# HomeAutomationModuleV2.net
KiCad netlist of a schematic drawn in EAGLE
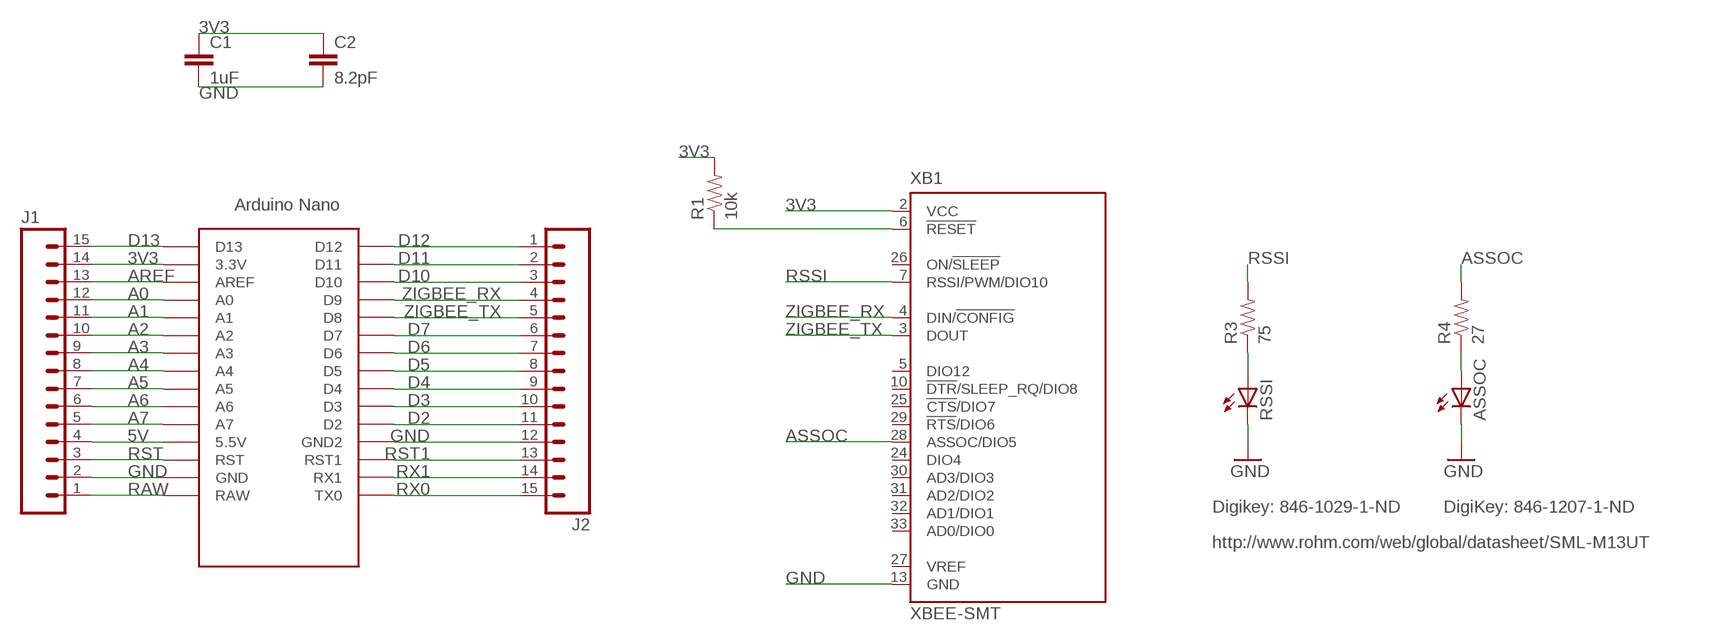
[diagram p0: schematic, sheet 1]

(export (version "E")
  (design (tool "Eeschema 10.0.6"))
  (components
    (comp (ref "ASSOC")
      (value "LEDCHIP-LED0805")
      (footprint "eagle-import:CHIP-LED0805")
      (libsource (lib "eagle-import") (part "LEDCHIP-LED0805"))
    )
    (comp (ref "C1")
      (value "1uF")
      (footprint "eagle-import:0805-CAP")
      (libsource (lib "eagle-import") (part "0.33UF-50V-10%(0805)"))
    )
    (comp (ref "C2")
      (value "8.2pF")
      (footprint "eagle-import:0805-CAP")
      (libsource (lib "eagle-import") (part "0.33UF-50V-10%(0805)"))
    )
    (comp (ref "J1")
      (value "M15")
      (footprint "eagle-import:1X15")
      (libsource (lib "eagle-import") (part "M15"))
    )
    (comp (ref "J2")
      (value "M15")
      (footprint "eagle-import:1X15")
      (libsource (lib "eagle-import") (part "M15"))
    )
    (comp (ref "R1")
      (value "10k")
      (footprint "eagle-import:0805")
      (libsource (lib "eagle-import") (part "0.3OHM-1/8W-1%(0805)"))
    )
    (comp (ref "R3")
      (value "75")
      (footprint "eagle-import:0805")
      (libsource (lib "eagle-import") (part "RESISTOR0805-RES"))
    )
    (comp (ref "R4")
      (value "27")
      (footprint "eagle-import:0805")
      (libsource (lib "eagle-import") (part "RESISTOR0805-RES"))
    )
    (comp (ref "RSSI")
      (value "LEDCHIP-LED0805")
      (footprint "eagle-import:CHIP-LED0805")
      (libsource (lib "eagle-import") (part "LEDCHIP-LED0805"))
    )
    (comp (ref "U$1")
      (value "NANO")
      (footprint "eagle-import:NANO")
      (libsource (lib "eagle-import") (part "NANO"))
    )
    (comp (ref "XB1")
      (value "XBEE-SMT")
      (footprint "eagle-import:XBEE-SMT")
      (libsource (lib "eagle-import") (part "XBEE-SMT"))
    )
  )
  (nets
    (net (code "1") (name "/3V3") (class "Default")
      (node (ref "C1") (pin "1") (pinfunction "1_1") (pintype "passive"))
      (node (ref "C2") (pin "1") (pinfunction "1_1") (pintype "passive"))
      (node (ref "J1") (pin "14") (pinfunction "14_14") (pintype "passive"))
      (node (ref "R1") (pin "2") (pinfunction "2_2") (pintype "passive"))
      (node (ref "U$1") (pin "3.3V") (pinfunction "3.3V_3.3V") (pintype "bidirectional"))
      (node (ref "XB1") (pin "2") (pinfunction "VCC_2") (pintype "power_in"))
    )
    (net (code "2") (name "/5V") (class "Default")
      (node (ref "J1") (pin "4") (pinfunction "4_4") (pintype "passive"))
      (node (ref "U$1") (pin "5V") (pinfunction "5.5V_5V") (pintype "bidirectional"))
    )
    (net (code "3") (name "/A0") (class "Default")
      (node (ref "J1") (pin "12") (pinfunction "12_12") (pintype "passive"))
      (node (ref "U$1") (pin "A0") (pinfunction "A0_A0") (pintype "bidirectional"))
    )
    (net (code "4") (name "/A1") (class "Default")
      (node (ref "J1") (pin "11") (pinfunction "11_11") (pintype "passive"))
      (node (ref "U$1") (pin "A1") (pinfunction "A1_A1") (pintype "bidirectional"))
    )
    (net (code "5") (name "/A2") (class "Default")
      (node (ref "J1") (pin "10") (pinfunction "10_10") (pintype "passive"))
      (node (ref "U$1") (pin "A2") (pinfunction "A2_A2") (pintype "bidirectional"))
    )
    (net (code "6") (name "/A3") (class "Default")
      (node (ref "J1") (pin "9") (pinfunction "9_9") (pintype "passive"))
      (node (ref "U$1") (pin "A3") (pinfunction "A3_A3") (pintype "bidirectional"))
    )
    (net (code "7") (name "/A4") (class "Default")
      (node (ref "J1") (pin "8") (pinfunction "8_8") (pintype "passive"))
      (node (ref "U$1") (pin "A4") (pinfunction "A4_A4") (pintype "bidirectional"))
    )
    (net (code "8") (name "/A5") (class "Default")
      (node (ref "J1") (pin "7") (pinfunction "7_7") (pintype "passive"))
      (node (ref "U$1") (pin "A5") (pinfunction "A5_A5") (pintype "bidirectional"))
    )
    (net (code "9") (name "/A6") (class "Default")
      (node (ref "J1") (pin "6") (pinfunction "6_6") (pintype "passive"))
      (node (ref "U$1") (pin "A6") (pinfunction "A6_A6") (pintype "bidirectional"))
    )
    (net (code "10") (name "/A7") (class "Default")
      (node (ref "J1") (pin "5") (pinfunction "5_5") (pintype "passive"))
      (node (ref "U$1") (pin "A7") (pinfunction "A7_A7") (pintype "bidirectional"))
    )
    (net (code "11") (name "/AREF") (class "Default")
      (node (ref "J1") (pin "13") (pinfunction "13_13") (pintype "passive"))
      (node (ref "U$1") (pin "AREF") (pinfunction "AREF_AREF") (pintype "bidirectional"))
    )
    (net (code "12") (name "/ASSOC") (class "Default")
      (node (ref "R4") (pin "2") (pinfunction "2_2") (pintype "passive"))
      (node (ref "XB1") (pin "28") (pinfunction "ASSOC/DIO5_28") (pintype "bidirectional"))
    )
    (net (code "13") (name "/D2") (class "Default")
      (node (ref "J2") (pin "11") (pinfunction "11_11") (pintype "passive"))
      (node (ref "U$1") (pin "D2") (pinfunction "D2_D2") (pintype "bidirectional"))
    )
    (net (code "14") (name "/D3") (class "Default")
      (node (ref "J2") (pin "10") (pinfunction "10_10") (pintype "passive"))
      (node (ref "U$1") (pin "D3") (pinfunction "D3_D3") (pintype "bidirectional"))
    )
    (net (code "15") (name "/D4") (class "Default")
      (node (ref "J2") (pin "9") (pinfunction "9_9") (pintype "passive"))
      (node (ref "U$1") (pin "D4") (pinfunction "D4_D4") (pintype "bidirectional"))
    )
    (net (code "16") (name "/D5") (class "Default")
      (node (ref "J2") (pin "8") (pinfunction "8_8") (pintype "passive"))
      (node (ref "U$1") (pin "D5") (pinfunction "D5_D5") (pintype "bidirectional"))
    )
    (net (code "17") (name "/D6") (class "Default")
      (node (ref "J2") (pin "7") (pinfunction "7_7") (pintype "passive"))
      (node (ref "U$1") (pin "D6") (pinfunction "D6_D6") (pintype "bidirectional"))
    )
    (net (code "18") (name "/D7") (class "Default")
      (node (ref "J2") (pin "6") (pinfunction "6_6") (pintype "passive"))
      (node (ref "U$1") (pin "D7") (pinfunction "D7_D7") (pintype "bidirectional"))
    )
    (net (code "19") (name "/D10") (class "Default")
      (node (ref "J2") (pin "3") (pinfunction "3_3") (pintype "passive"))
      (node (ref "U$1") (pin "D10") (pinfunction "D10_D10") (pintype "bidirectional"))
    )
    (net (code "20") (name "/D11") (class "Default")
      (node (ref "J2") (pin "2") (pinfunction "2_2") (pintype "passive"))
      (node (ref "U$1") (pin "D11") (pinfunction "D11_D11") (pintype "bidirectional"))
    )
    (net (code "21") (name "/D12") (class "Default")
      (node (ref "J2") (pin "1") (pinfunction "1_1") (pintype "passive"))
      (node (ref "U$1") (pin "D12") (pinfunction "D12_D12") (pintype "bidirectional"))
    )
    (net (code "22") (name "/D13") (class "Default")
      (node (ref "J1") (pin "15") (pinfunction "15_15") (pintype "passive"))
      (node (ref "U$1") (pin "D13") (pinfunction "D13_D13") (pintype "bidirectional"))
    )
    (net (code "23") (name "/RAW") (class "Default")
      (node (ref "J1") (pin "1") (pinfunction "1_1") (pintype "passive"))
      (node (ref "U$1") (pin "RAW") (pinfunction "RAW_RAW") (pintype "bidirectional"))
    )
    (net (code "24") (name "/RSSI") (class "Default")
      (node (ref "R3") (pin "2") (pinfunction "2_2") (pintype "passive"))
      (node (ref "XB1") (pin "7") (pinfunction "RSSI/PWM/DIO10_7") (pintype "output"))
    )
    (net (code "25") (name "/RST") (class "Default")
      (node (ref "J1") (pin "3") (pinfunction "3_3") (pintype "passive"))
      (node (ref "U$1") (pin "RST") (pinfunction "RST_RST") (pintype "bidirectional"))
    )
    (net (code "26") (name "/RST1") (class "Default")
      (node (ref "J2") (pin "13") (pinfunction "13_13") (pintype "passive"))
      (node (ref "U$1") (pin "RST1") (pinfunction "RST1_RST1") (pintype "bidirectional"))
    )
    (net (code "27") (name "/RX0") (class "Default")
      (node (ref "J2") (pin "15") (pinfunction "15_15") (pintype "passive"))
      (node (ref "U$1") (pin "TX0") (pinfunction "TX0_TX0") (pintype "bidirectional"))
    )
    (net (code "28") (name "/RX1") (class "Default")
      (node (ref "J2") (pin "14") (pinfunction "14_14") (pintype "passive"))
      (node (ref "U$1") (pin "RX1") (pinfunction "RX1_RX1") (pintype "bidirectional"))
    )
    (net (code "29") (name "/ZIGBEE_RX") (class "Default")
      (node (ref "J2") (pin "4") (pinfunction "4_4") (pintype "passive"))
      (node (ref "U$1") (pin "D9") (pinfunction "D9_D9") (pintype "bidirectional"))
      (node (ref "XB1") (pin "4") (pinfunction "DIN/~{CONFIG}_4") (pintype "input"))
    )
    (net (code "30") (name "/ZIGBEE_TX") (class "Default")
      (node (ref "J2") (pin "5") (pinfunction "5_5") (pintype "passive"))
      (node (ref "U$1") (pin "D8") (pinfunction "D8_D8") (pintype "bidirectional"))
      (node (ref "XB1") (pin "3") (pinfunction "DOUT_3") (pintype "output"))
    )
    (net (code "31") (name "GND") (class "Default")
      (node (ref "ASSOC") (pin "C") (pinfunction "C_C") (pintype "passive"))
      (node (ref "C1") (pin "2") (pinfunction "2_2") (pintype "passive"))
      (node (ref "C2") (pin "2") (pinfunction "2_2") (pintype "passive"))
      (node (ref "J1") (pin "2") (pinfunction "2_2") (pintype "passive"))
      (node (ref "J2") (pin "12") (pinfunction "12_12") (pintype "passive"))
      (node (ref "RSSI") (pin "C") (pinfunction "C_C") (pintype "passive"))
      (node (ref "U$1") (pin "GND") (pinfunction "GND_GND") (pintype "bidirectional"))
      (node (ref "U$1") (pin "GND1") (pinfunction "GND2_GND1") (pintype "bidirectional"))
      (node (ref "XB1") (pin "13") (pinfunction "GND_13") (pintype "power_in"))
    )
    (net (code "32") (name "Net-(ASSOC-PadA)") (class "Default")
      (node (ref "ASSOC") (pin "A") (pinfunction "A_A") (pintype "passive"))
      (node (ref "R4") (pin "1") (pinfunction "1_1") (pintype "passive"))
    )
    (net (code "33") (name "Net-(R3-Pad1)") (class "Default")
      (node (ref "R3") (pin "1") (pinfunction "1_1") (pintype "passive"))
      (node (ref "RSSI") (pin "A") (pinfunction "A_A") (pintype "passive"))
    )
    (net (code "34") (name "Net-(XB1-~{RESET})") (class "Default")
      (node (ref "R1") (pin "1") (pinfunction "1_1") (pintype "passive"))
      (node (ref "XB1") (pin "6") (pinfunction "~{RESET}_6") (pintype "input"))
    )
    (net (code "35") (name "unconnected-(U$1-PadICSP1)") (class "Default")
      (node (ref "U$1") (pin "ICSP1") (pinfunction "ICSP1_ICSP1") (pintype "bidirectional"))
    )
    (net (code "36") (name "unconnected-(U$1-PadICSP2)") (class "Default")
      (node (ref "U$1") (pin "ICSP2") (pinfunction "ICSP2_ICSP2") (pintype "bidirectional"))
    )
    (net (code "37") (name "unconnected-(U$1-PadICSP3)") (class "Default")
      (node (ref "U$1") (pin "ICSP3") (pinfunction "ICSP3_ICSP3") (pintype "bidirectional"))
    )
    (net (code "38") (name "unconnected-(U$1-PadICSP4)") (class "Default")
      (node (ref "U$1") (pin "ICSP4") (pinfunction "ICSP4_ICSP4") (pintype "bidirectional"))
    )
    (net (code "39") (name "unconnected-(U$1-PadICSP5)") (class "Default")
      (node (ref "U$1") (pin "ICSP5") (pinfunction "ICSP5_ICSP5") (pintype "bidirectional"))
    )
    (net (code "40") (name "unconnected-(U$1-PadICSP6)") (class "Default")
      (node (ref "U$1") (pin "ICSP6") (pinfunction "ICSP6_ICSP6") (pintype "bidirectional"))
    )
    (net (code "41") (name "unconnected-(XB1-AD0{slash}DIO0-Pad33)") (class "Default")
      (node (ref "XB1") (pin "33") (pinfunction "AD0/DIO0_33") (pintype "bidirectional"))
    )
    (net (code "42") (name "unconnected-(XB1-AD1{slash}DIO1-Pad32)") (class "Default")
      (node (ref "XB1") (pin "32") (pinfunction "AD1/DIO1_32") (pintype "bidirectional"))
    )
    (net (code "43") (name "unconnected-(XB1-AD2{slash}DIO2-Pad31)") (class "Default")
      (node (ref "XB1") (pin "31") (pinfunction "AD2/DIO2_31") (pintype "bidirectional"))
    )
    (net (code "44") (name "unconnected-(XB1-AD3{slash}DIO3-Pad30)") (class "Default")
      (node (ref "XB1") (pin "30") (pinfunction "AD3/DIO3_30") (pintype "bidirectional"))
    )
    (net (code "45") (name "unconnected-(XB1-DIO4-Pad24)") (class "Default")
      (node (ref "XB1") (pin "24") (pinfunction "DIO4_24") (pintype "bidirectional"))
    )
    (net (code "46") (name "unconnected-(XB1-DIO12-Pad5)") (class "Default")
      (node (ref "XB1") (pin "5") (pinfunction "DIO12_5") (pintype "bidirectional"))
    )
    (net (code "47") (name "unconnected-(XB1-ON{slash}~{SLEEP}-Pad26)") (class "Default")
      (node (ref "XB1") (pin "26") (pinfunction "ON/~{SLEEP}_26") (pintype "output"))
    )
    (net (code "48") (name "unconnected-(XB1-VREF-Pad27)") (class "Default")
      (node (ref "XB1") (pin "27") (pinfunction "VREF_27") (pintype "input"))
    )
    (net (code "49") (name "unconnected-(XB1-~{CTS}{slash}DIO7-Pad25)") (class "Default")
      (node (ref "XB1") (pin "25") (pinfunction "~{CTS}/DIO7_25") (pintype "bidirectional"))
    )
    (net (code "50") (name "unconnected-(XB1-~{DTR}{slash}SLEEP_RQ{slash}DIO8-Pad10)") (class "Default")
      (node (ref "XB1") (pin "10") (pinfunction "~{DTR}/SLEEP_RQ/DIO8_10") (pintype "bidirectional"))
    )
    (net (code "51") (name "unconnected-(XB1-~{RTS}{slash}DIO6-Pad29)") (class "Default")
      (node (ref "XB1") (pin "29") (pinfunction "~{RTS}/DIO6_29") (pintype "bidirectional"))
    )
  )
)
